# Raspi_Power.net
KiCad netlist of a schematic drawn in EAGLE
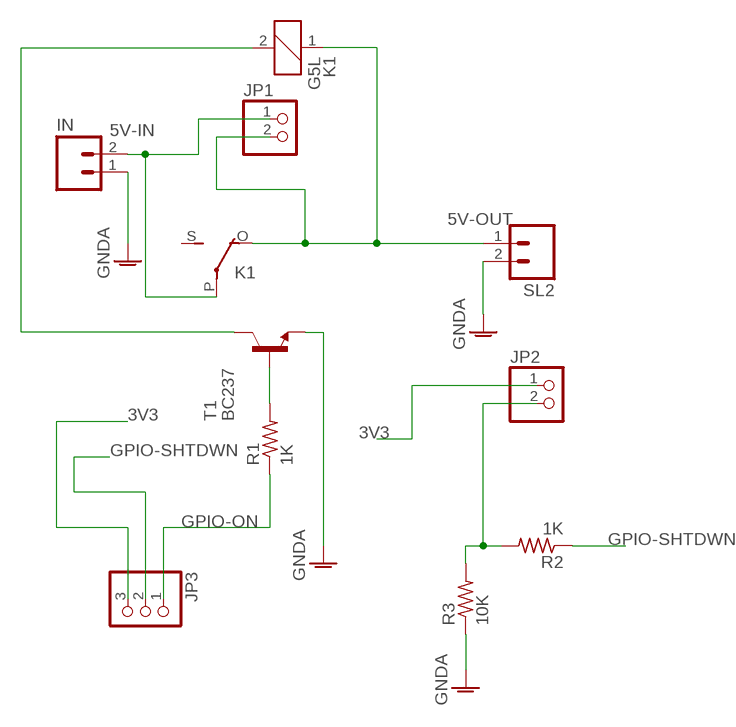
[diagram p0: schematic, sheet 1]

(export (version "E")
  (design (tool "Eeschema 10.0.6"))
  (components
    (comp (ref "IN")
      (value "M02")
      (footprint "eagle-import:02P")
      (libsource (lib "eagle-import") (part "M02"))
    )
    (comp (ref "JP1")
      (value "PINHD-1X2")
      (footprint "eagle-import:1X02")
      (libsource (lib "eagle-import") (part "PINHD-1X2"))
    )
    (comp (ref "JP2")
      (value "PINHD-1X2")
      (footprint "eagle-import:1X02")
      (libsource (lib "eagle-import") (part "PINHD-1X2"))
    )
    (comp (ref "JP3")
      (value "PINHD-1X3")
      (footprint "eagle-import:1X03")
      (libsource (lib "eagle-import") (part "PINHD-1X3"))
    )
    (comp (ref "K1")
      (value "G5L")
      (footprint "eagle-import:G5LE")
      (libsource (lib "eagle-import") (part "G5L"))
    )
    (comp (ref "R1")
      (value "1K")
      (footprint "eagle-import:0204_7")
      (libsource (lib "eagle-import") (part "R-US_0204/7"))
    )
    (comp (ref "R2")
      (value "1K")
      (footprint "eagle-import:0204_7")
      (libsource (lib "eagle-import") (part "R-US_0204/7"))
    )
    (comp (ref "R3")
      (value "10K")
      (footprint "eagle-import:0204_7")
      (libsource (lib "eagle-import") (part "R-US_0204/7"))
    )
    (comp (ref "SL2")
      (value "M02")
      (footprint "eagle-import:02P")
      (libsource (lib "eagle-import") (part "M02"))
    )
    (comp (ref "T1")
      (value "BC237")
      (footprint "eagle-import:TO92")
      (libsource (lib "eagle-import") (part "BC237"))
    )
  )
  (nets
    (net (code "1") (name "/3V3") (class "Default")
      (node (ref "JP2") (pin "1") (pinfunction "1_1") (pintype "passive"))
      (node (ref "JP3") (pin "3") (pinfunction "3_3") (pintype "passive"))
    )
    (net (code "2") (name "/5V-IN") (class "Default")
      (node (ref "IN") (pin "2") (pinfunction "2_2") (pintype "passive"))
      (node (ref "JP1") (pin "1") (pinfunction "1_1") (pintype "passive"))
      (node (ref "K1") (pin "P") (pinfunction "P_P") (pintype "passive"))
    )
    (net (code "3") (name "/5V-OUT") (class "Default")
      (node (ref "JP1") (pin "2") (pinfunction "2_2") (pintype "passive"))
      (node (ref "K1") (pin "1") (pinfunction "1_1") (pintype "passive"))
      (node (ref "K1") (pin "O") (pinfunction "O_O") (pintype "passive"))
      (node (ref "SL2") (pin "1") (pinfunction "1_1") (pintype "passive"))
    )
    (net (code "4") (name "/GPIO-ON") (class "Default")
      (node (ref "JP3") (pin "1") (pinfunction "1_1") (pintype "passive"))
      (node (ref "R1") (pin "1") (pinfunction "1_1") (pintype "passive"))
    )
    (net (code "5") (name "/GPIO-SHTDWN") (class "Default")
      (node (ref "JP3") (pin "2") (pinfunction "2_2") (pintype "passive"))
      (node (ref "R2") (pin "1") (pinfunction "1_1") (pintype "passive"))
    )
    (net (code "6") (name "GNDA") (class "Default")
      (node (ref "IN") (pin "1") (pinfunction "1_1") (pintype "passive"))
      (node (ref "R3") (pin "1") (pinfunction "1_1") (pintype "passive"))
      (node (ref "SL2") (pin "2") (pinfunction "2_2") (pintype "passive"))
      (node (ref "T1") (pin "1") (pinfunction "E_1") (pintype "passive"))
    )
    (net (code "7") (name "Net-(JP2-Pad2)") (class "Default")
      (node (ref "JP2") (pin "2") (pinfunction "2_2") (pintype "passive"))
      (node (ref "R2") (pin "2") (pinfunction "2_2") (pintype "passive"))
      (node (ref "R3") (pin "2") (pinfunction "2_2") (pintype "passive"))
    )
    (net (code "8") (name "Net-(T1-B)") (class "Default")
      (node (ref "R1") (pin "2") (pinfunction "2_2") (pintype "passive"))
      (node (ref "T1") (pin "2") (pinfunction "B_2") (pintype "passive"))
    )
    (net (code "9") (name "Net-(T1-C)") (class "Default")
      (node (ref "K1") (pin "2") (pinfunction "2_2") (pintype "passive"))
      (node (ref "T1") (pin "3") (pinfunction "C_3") (pintype "passive"))
    )
    (net (code "10") (name "unconnected-(K1-PadS)") (class "Default")
      (node (ref "K1") (pin "S") (pinfunction "S_S") (pintype "passive"))
    )
  )
)
